# FPGA_Transcievers.net
KiCad netlist of a schematic drawn in Altium Designer
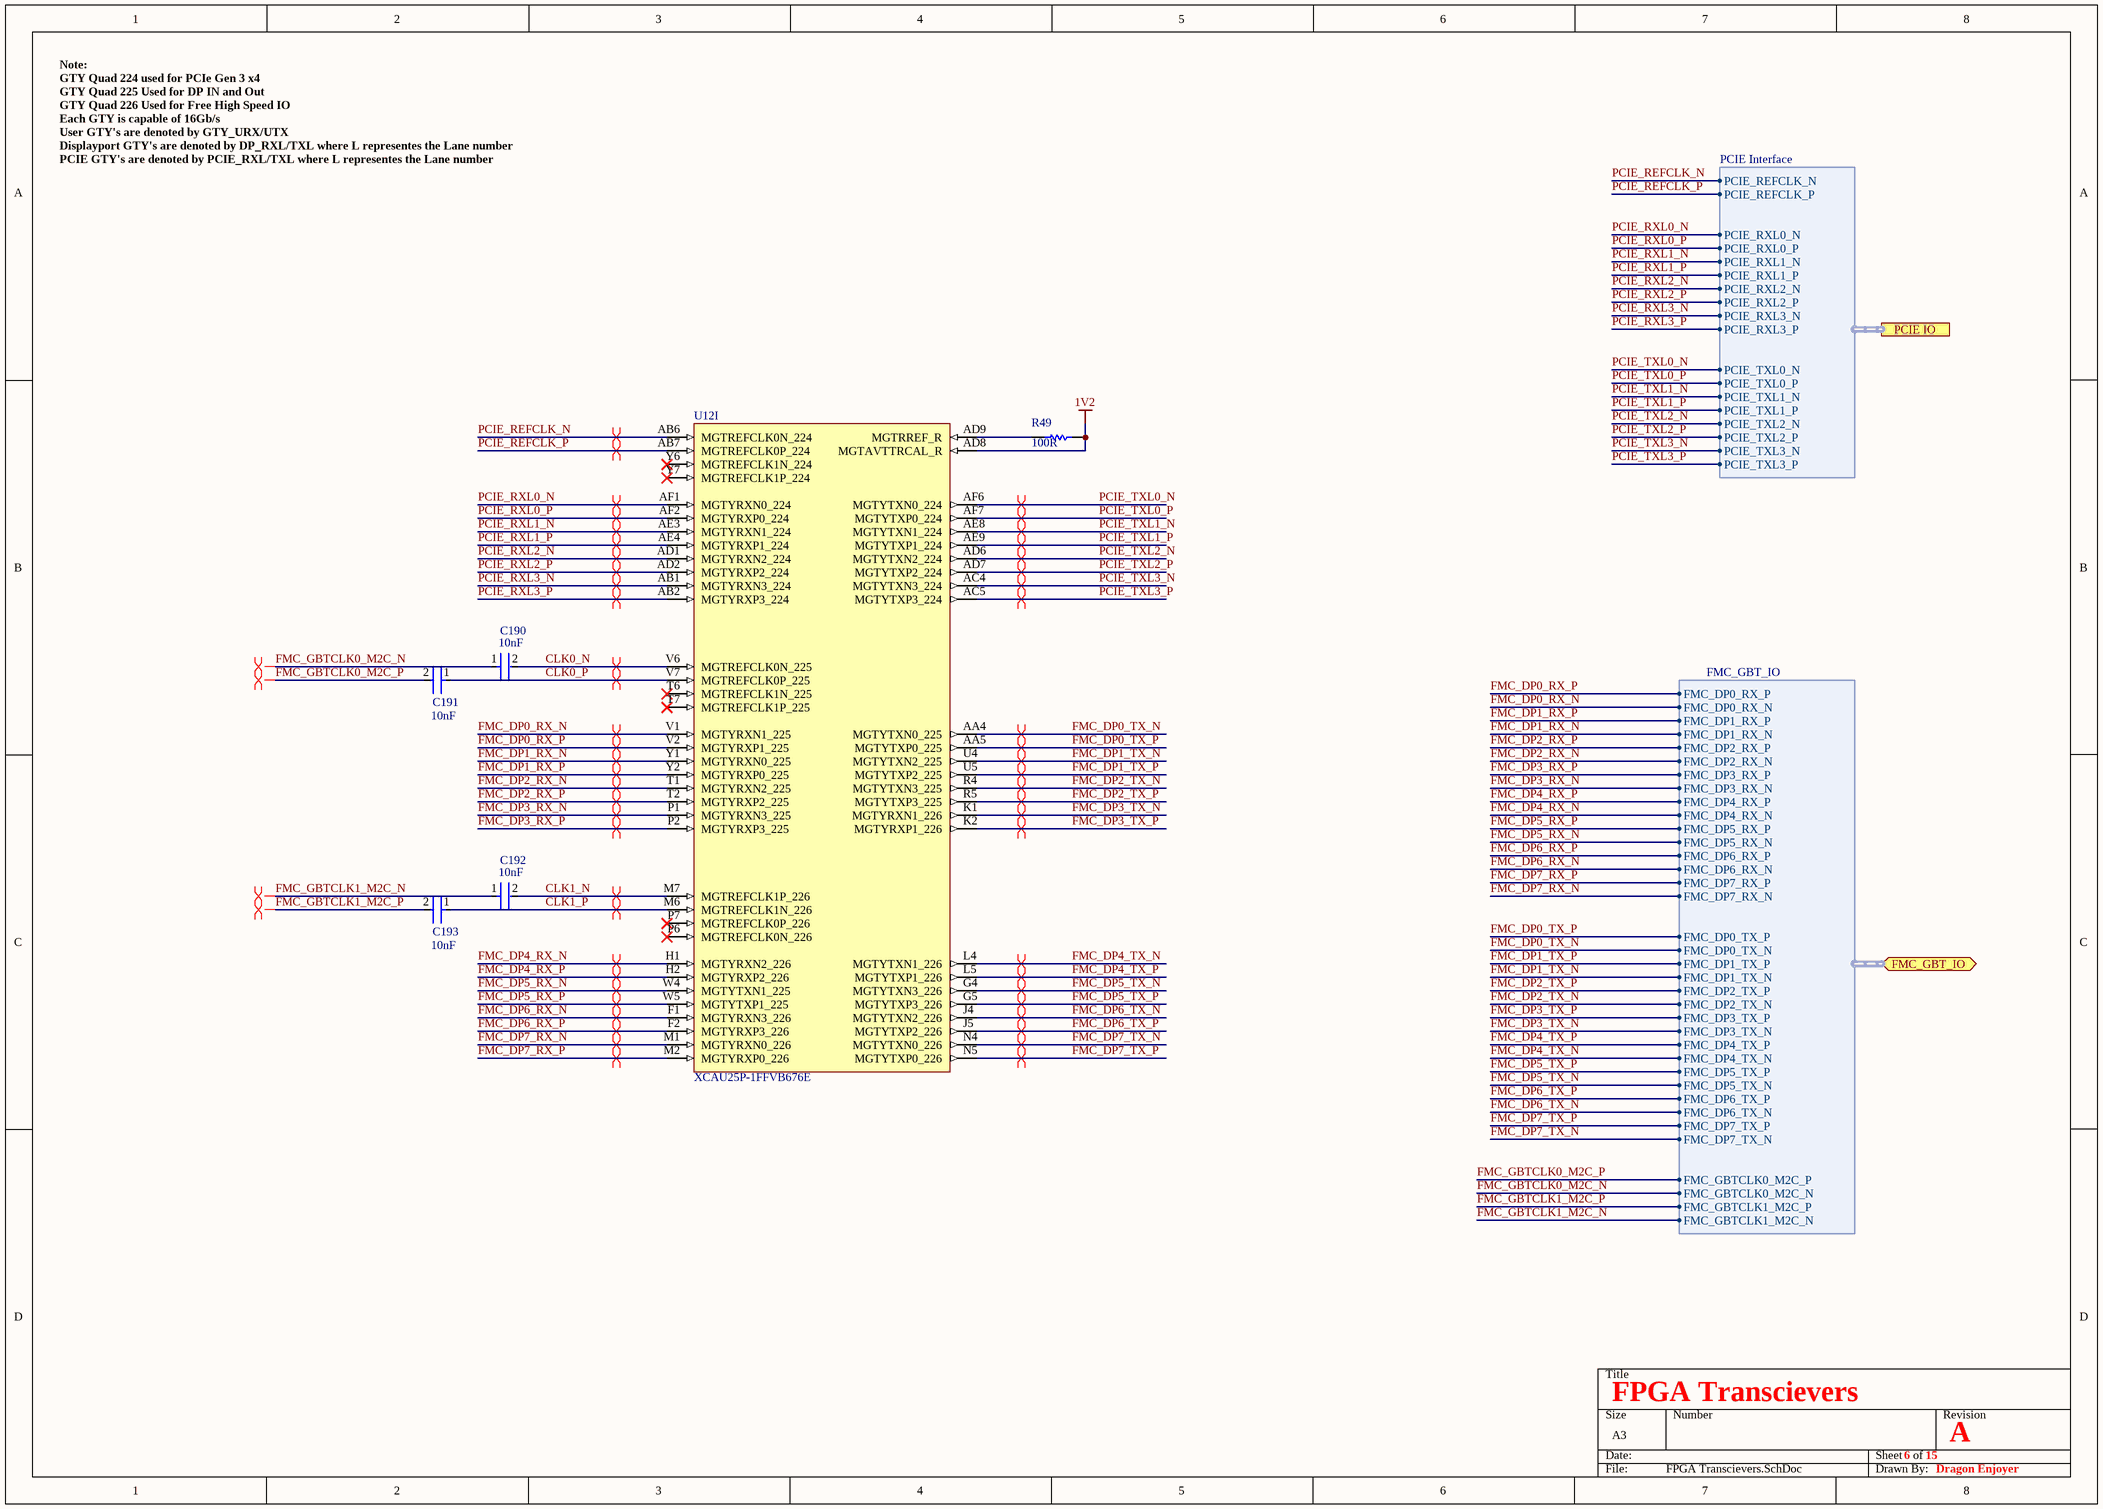
[diagram p0: FPGA Transcievers.SchDoc]

(export (version "E")
  (design (tool "Eeschema 10.0.6"))
  (components
    (comp (ref "C190")
      (value "GRM155R71H103KA88D")
      (footprint "FP-GRM155-0_05-IPC_C")
      (description "Chip Multilayer Ceramic Capacitors for General Purpose, 0402, 10000pF, X7R, 15%, 10%, 50V")
      (fields
        (field (name "TOLERANCE") "10%")
        (field (name "VOLTAGE") "25V")
        (field (name "CAPACITANCE") "10nF")
      )
      (libsource (lib "Altium Content Vault") (part "02cd4be3c70576c341d710602a673aa"))
    )
    (comp (ref "C191")
      (value "GRM155R71H103KA88D")
      (footprint "FP-GRM155-0_05-IPC_C")
      (description "Chip Multilayer Ceramic Capacitors for General Purpose, 0402, 10000pF, X7R, 15%, 10%, 50V")
      (fields
        (field (name "TOLERANCE") "10%")
        (field (name "VOLTAGE") "25V")
        (field (name "CAPACITANCE") "10nF")
      )
      (libsource (lib "Altium Content Vault") (part "02cd4be3c70576c341d710602a673aa"))
    )
    (comp (ref "C192")
      (value "GRM155R71H103KA88D")
      (footprint "FP-GRM155-0_05-IPC_C")
      (description "Chip Multilayer Ceramic Capacitors for General Purpose, 0402, 10000pF, X7R, 15%, 10%, 50V")
      (fields
        (field (name "TOLERANCE") "10%")
        (field (name "VOLTAGE") "25V")
        (field (name "CAPACITANCE") "10nF")
      )
      (libsource (lib "Altium Content Vault") (part "02cd4be3c70576c341d710602a673aa"))
    )
    (comp (ref "C193")
      (value "GRM155R71H103KA88D")
      (footprint "FP-GRM155-0_05-IPC_C")
      (description "Chip Multilayer Ceramic Capacitors for General Purpose, 0402, 10000pF, X7R, 15%, 10%, 50V")
      (fields
        (field (name "TOLERANCE") "10%")
        (field (name "VOLTAGE") "25V")
        (field (name "CAPACITANCE") "10nF")
      )
      (libsource (lib "Altium Content Vault") (part "02cd4be3c70576c341d710602a673aa"))
    )
    (comp (ref "R49")
      (value "100R")
      (footprint "RESC1005X40X25ML05T10")
      (fields (field (name "PART NUMBER") "RC0402FR-07100RL") (field (name "MANUFACTURER") "Yageo / Phycomp"))
      (libsource (lib "Altium Content Vault") (part "RES"))
    )
    (comp (ref "U12")
      (value "XCAU25P-1FFVB676E")
      (footprint "BGA676C100P26X26_2600X2600X352")
      (description "FPGA XCAU25 Family 308437 Logic Units 308437 Cells 0.85V 676-Pin FCBGA")
      (libsource (lib "Main Workspace") (part "XCAU25P-1FFVB676E"))
    )
  )
  (nets
    (net (code "4") (name "/CLK0_N") (class "Default")
      (node (ref "C190") (pin "2") (pinfunction "2_2") (pintype "passive"))
      (node (ref "U12") (pin "V6") (pinfunction "MGTREFCLK0N_225_V6") (pintype "input"))
    )
    (net (code "5") (name "/CLK0_P") (class "Default")
      (node (ref "C191") (pin "1") (pinfunction "1_1") (pintype "passive"))
      (node (ref "U12") (pin "V7") (pinfunction "MGTREFCLK0P_225_V7") (pintype "input"))
    )
    (net (code "6") (name "/CLK1_N") (class "Default")
      (node (ref "C192") (pin "2") (pinfunction "2_2") (pintype "passive"))
      (node (ref "U12") (pin "M7") (pinfunction "MGTREFCLK1P_226_M7") (pintype "input"))
    )
    (net (code "7") (name "/CLK1_P") (class "Default")
      (node (ref "C193") (pin "1") (pinfunction "1_1") (pintype "passive"))
      (node (ref "U12") (pin "M6") (pinfunction "MGTREFCLK1N_226_M6") (pintype "input"))
    )
    (net (code "8") (name "/FMC_DP0_RX_N") (class "Default")
      (node (ref "U12") (pin "V1") (pinfunction "MGTYRXN1_225_V1") (pintype "input"))
    )
    (net (code "9") (name "/FMC_DP0_RX_P") (class "Default")
      (node (ref "U12") (pin "V2") (pinfunction "MGTYRXP1_225_V2") (pintype "input"))
    )
    (net (code "10") (name "/FMC_DP0_TX_N") (class "Default")
      (node (ref "U12") (pin "AA4") (pinfunction "MGTYTXN0_225_AA4") (pintype "output"))
    )
    (net (code "11") (name "/FMC_DP0_TX_P") (class "Default")
      (node (ref "U12") (pin "AA5") (pinfunction "MGTYTXP0_225_AA5") (pintype "output"))
    )
    (net (code "12") (name "/FMC_DP1_RX_N") (class "Default")
      (node (ref "U12") (pin "Y1") (pinfunction "MGTYRXN0_225_Y1") (pintype "input"))
    )
    (net (code "13") (name "/FMC_DP1_RX_P") (class "Default")
      (node (ref "U12") (pin "Y2") (pinfunction "MGTYRXP0_225_Y2") (pintype "input"))
    )
    (net (code "14") (name "/FMC_DP1_TX_N") (class "Default")
      (node (ref "U12") (pin "U4") (pinfunction "MGTYTXN2_225_U4") (pintype "output"))
    )
    (net (code "15") (name "/FMC_DP1_TX_P") (class "Default")
      (node (ref "U12") (pin "U5") (pinfunction "MGTYTXP2_225_U5") (pintype "output"))
    )
    (net (code "16") (name "/FMC_DP2_RX_N") (class "Default")
      (node (ref "U12") (pin "T1") (pinfunction "MGTYRXN2_225_T1") (pintype "input"))
    )
    (net (code "17") (name "/FMC_DP2_RX_P") (class "Default")
      (node (ref "U12") (pin "T2") (pinfunction "MGTYRXP2_225_T2") (pintype "input"))
    )
    (net (code "18") (name "/FMC_DP2_TX_N") (class "Default")
      (node (ref "U12") (pin "R4") (pinfunction "MGTYTXN3_225_R4") (pintype "output"))
    )
    (net (code "19") (name "/FMC_DP2_TX_P") (class "Default")
      (node (ref "U12") (pin "R5") (pinfunction "MGTYTXP3_225_R5") (pintype "output"))
    )
    (net (code "20") (name "/FMC_DP3_RX_N") (class "Default")
      (node (ref "U12") (pin "P1") (pinfunction "MGTYRXN3_225_P1") (pintype "input"))
    )
    (net (code "21") (name "/FMC_DP3_RX_P") (class "Default")
      (node (ref "U12") (pin "P2") (pinfunction "MGTYRXP3_225_P2") (pintype "input"))
    )
    (net (code "22") (name "/FMC_DP3_TX_N") (class "Default")
      (node (ref "U12") (pin "K1") (pinfunction "MGTYRXN1_226_K1") (pintype "output"))
    )
    (net (code "23") (name "/FMC_DP3_TX_P") (class "Default")
      (node (ref "U12") (pin "K2") (pinfunction "MGTYRXP1_226_K2") (pintype "output"))
    )
    (net (code "24") (name "/FMC_DP4_RX_N") (class "Default")
      (node (ref "U12") (pin "H1") (pinfunction "MGTYRXN2_226_H1") (pintype "input"))
    )
    (net (code "25") (name "/FMC_DP4_RX_P") (class "Default")
      (node (ref "U12") (pin "H2") (pinfunction "MGTYRXP2_226_H2") (pintype "input"))
    )
    (net (code "26") (name "/FMC_DP4_TX_N") (class "Default")
      (node (ref "U12") (pin "L4") (pinfunction "MGTYTXN1_226_L4") (pintype "output"))
    )
    (net (code "27") (name "/FMC_DP4_TX_P") (class "Default")
      (node (ref "U12") (pin "L5") (pinfunction "MGTYTXP1_226_L5") (pintype "output"))
    )
    (net (code "28") (name "/FMC_DP5_RX_N") (class "Default")
      (node (ref "U12") (pin "W4") (pinfunction "MGTYTXN1_225_W4") (pintype "input"))
    )
    (net (code "29") (name "/FMC_DP5_RX_P") (class "Default")
      (node (ref "U12") (pin "W5") (pinfunction "MGTYTXP1_225_W5") (pintype "input"))
    )
    (net (code "30") (name "/FMC_DP5_TX_N") (class "Default")
      (node (ref "U12") (pin "G4") (pinfunction "MGTYTXN3_226_G4") (pintype "output"))
    )
    (net (code "31") (name "/FMC_DP5_TX_P") (class "Default")
      (node (ref "U12") (pin "G5") (pinfunction "MGTYTXP3_226_G5") (pintype "output"))
    )
    (net (code "32") (name "/FMC_DP6_RX_N") (class "Default")
      (node (ref "U12") (pin "F1") (pinfunction "MGTYRXN3_226_F1") (pintype "input"))
    )
    (net (code "33") (name "/FMC_DP6_RX_P") (class "Default")
      (node (ref "U12") (pin "F2") (pinfunction "MGTYRXP3_226_F2") (pintype "input"))
    )
    (net (code "34") (name "/FMC_DP6_TX_N") (class "Default")
      (node (ref "U12") (pin "J4") (pinfunction "MGTYTXN2_226_J4") (pintype "output"))
    )
    (net (code "35") (name "/FMC_DP6_TX_P") (class "Default")
      (node (ref "U12") (pin "J5") (pinfunction "MGTYTXP2_226_J5") (pintype "output"))
    )
    (net (code "36") (name "/FMC_DP7_RX_N") (class "Default")
      (node (ref "U12") (pin "M1") (pinfunction "MGTYRXN0_226_M1") (pintype "input"))
    )
    (net (code "37") (name "/FMC_DP7_RX_P") (class "Default")
      (node (ref "U12") (pin "M2") (pinfunction "MGTYRXP0_226_M2") (pintype "input"))
    )
    (net (code "38") (name "/FMC_DP7_TX_N") (class "Default")
      (node (ref "U12") (pin "N4") (pinfunction "MGTYTXN0_226_N4") (pintype "output"))
    )
    (net (code "39") (name "/FMC_DP7_TX_P") (class "Default")
      (node (ref "U12") (pin "N5") (pinfunction "MGTYTXP0_226_N5") (pintype "output"))
    )
    (net (code "40") (name "/FMC_GBTCLK0_M2C_N") (class "Default")
      (node (ref "C190") (pin "1") (pinfunction "1_1") (pintype "passive"))
    )
    (net (code "41") (name "/FMC_GBTCLK0_M2C_P") (class "Default")
      (node (ref "C191") (pin "2") (pinfunction "2_2") (pintype "passive"))
    )
    (net (code "42") (name "/FMC_GBTCLK1_M2C_N") (class "Default")
      (node (ref "C192") (pin "1") (pinfunction "1_1") (pintype "passive"))
    )
    (net (code "43") (name "/FMC_GBTCLK1_M2C_P") (class "Default")
      (node (ref "C193") (pin "2") (pinfunction "2_2") (pintype "passive"))
    )
    (net (code "44") (name "/PCIE_REFCLK_N") (class "Default")
      (node (ref "U12") (pin "AB6") (pinfunction "MGTREFCLK0N_224_AB6") (pintype "input"))
    )
    (net (code "45") (name "/PCIE_REFCLK_P") (class "Default")
      (node (ref "U12") (pin "AB7") (pinfunction "MGTREFCLK0P_224_AB7") (pintype "input"))
    )
    (net (code "46") (name "/PCIE_RXL0_N") (class "Default")
      (node (ref "U12") (pin "AF1") (pinfunction "MGTYRXN0_224_AF1") (pintype "input"))
    )
    (net (code "47") (name "/PCIE_RXL0_P") (class "Default")
      (node (ref "U12") (pin "AF2") (pinfunction "MGTYRXP0_224_AF2") (pintype "input"))
    )
    (net (code "48") (name "/PCIE_RXL1_N") (class "Default")
      (node (ref "U12") (pin "AE3") (pinfunction "MGTYRXN1_224_AE3") (pintype "input"))
    )
    (net (code "49") (name "/PCIE_RXL1_P") (class "Default")
      (node (ref "U12") (pin "AE4") (pinfunction "MGTYRXP1_224_AE4") (pintype "input"))
    )
    (net (code "50") (name "/PCIE_RXL2_N") (class "Default")
      (node (ref "U12") (pin "AD1") (pinfunction "MGTYRXN2_224_AD1") (pintype "input"))
    )
    (net (code "51") (name "/PCIE_RXL2_P") (class "Default")
      (node (ref "U12") (pin "AD2") (pinfunction "MGTYRXP2_224_AD2") (pintype "input"))
    )
    (net (code "52") (name "/PCIE_RXL3_N") (class "Default")
      (node (ref "U12") (pin "AB1") (pinfunction "MGTYRXN3_224_AB1") (pintype "input"))
    )
    (net (code "53") (name "/PCIE_RXL3_P") (class "Default")
      (node (ref "U12") (pin "AB2") (pinfunction "MGTYRXP3_224_AB2") (pintype "input"))
    )
    (net (code "54") (name "/PCIE_TXL0_N") (class "Default")
      (node (ref "U12") (pin "AF6") (pinfunction "MGTYTXN0_224_AF6") (pintype "output"))
    )
    (net (code "55") (name "/PCIE_TXL0_P") (class "Default")
      (node (ref "U12") (pin "AF7") (pinfunction "MGTYTXP0_224_AF7") (pintype "output"))
    )
    (net (code "56") (name "/PCIE_TXL1_N") (class "Default")
      (node (ref "U12") (pin "AE8") (pinfunction "MGTYTXN1_224_AE8") (pintype "output"))
    )
    (net (code "57") (name "/PCIE_TXL1_P") (class "Default")
      (node (ref "U12") (pin "AE9") (pinfunction "MGTYTXP1_224_AE9") (pintype "output"))
    )
    (net (code "58") (name "/PCIE_TXL2_N") (class "Default")
      (node (ref "U12") (pin "AD6") (pinfunction "MGTYTXN2_224_AD6") (pintype "output"))
    )
    (net (code "59") (name "/PCIE_TXL2_P") (class "Default")
      (node (ref "U12") (pin "AD7") (pinfunction "MGTYTXP2_224_AD7") (pintype "output"))
    )
    (net (code "60") (name "/PCIE_TXL3_N") (class "Default")
      (node (ref "U12") (pin "AC4") (pinfunction "MGTYTXN3_224_AC4") (pintype "output"))
    )
    (net (code "61") (name "/PCIE_TXL3_P") (class "Default")
      (node (ref "U12") (pin "AC5") (pinfunction "MGTYTXP3_224_AC5") (pintype "output"))
    )
    (net (code "64") (name "1V2") (class "Default")
      (node (ref "R49") (pin "2") (pinfunction "2_2") (pintype "passive"))
      (node (ref "U12") (pin "AD8") (pinfunction "MGTAVTTRCAL_R_AD8") (pintype "input"))
    )
    (net (code "65") (name "Net-(U12I-MGTRREF_R)") (class "Default")
      (node (ref "R49") (pin "1") (pinfunction "1_1") (pintype "passive"))
      (node (ref "U12") (pin "AD9") (pinfunction "MGTRREF_R_AD9") (pintype "input"))
    )
    (net (code "66") (name "unconnected-(U12I-MGTREFCLK0N_226-PadP6)") (class "Default")
      (node (ref "U12") (pin "P6") (pinfunction "MGTREFCLK0N_226_P6") (pintype "input+no_connect"))
    )
    (net (code "67") (name "unconnected-(U12I-MGTREFCLK0P_226-PadP7)") (class "Default")
      (node (ref "U12") (pin "P7") (pinfunction "MGTREFCLK0P_226_P7") (pintype "input+no_connect"))
    )
    (net (code "68") (name "unconnected-(U12I-MGTREFCLK1N_224-PadY6)") (class "Default")
      (node (ref "U12") (pin "Y6") (pinfunction "MGTREFCLK1N_224_Y6") (pintype "input+no_connect"))
    )
    (net (code "69") (name "unconnected-(U12I-MGTREFCLK1N_225-PadT6)") (class "Default")
      (node (ref "U12") (pin "T6") (pinfunction "MGTREFCLK1N_225_T6") (pintype "input+no_connect"))
    )
    (net (code "70") (name "unconnected-(U12I-MGTREFCLK1P_224-PadY7)") (class "Default")
      (node (ref "U12") (pin "Y7") (pinfunction "MGTREFCLK1P_224_Y7") (pintype "input+no_connect"))
    )
    (net (code "71") (name "unconnected-(U12I-MGTREFCLK1P_225-PadT7)") (class "Default")
      (node (ref "U12") (pin "T7") (pinfunction "MGTREFCLK1P_225_T7") (pintype "input+no_connect"))
    )
  )
)
